# Power.net
KiCad netlist of a schematic drawn in Altium Designer
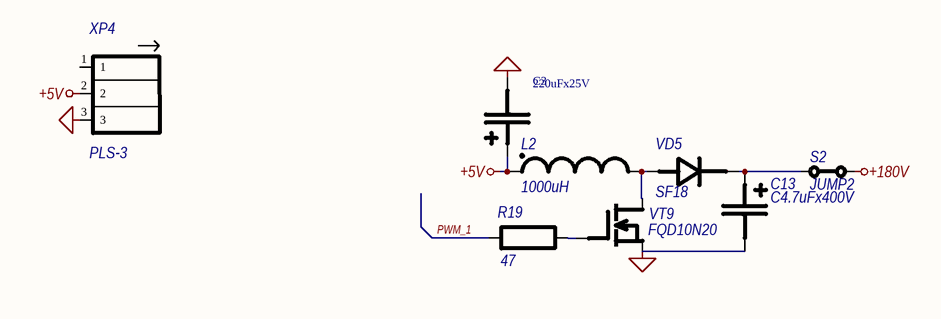
[diagram p0: Power.SchDoc]

(export (version "E")
  (design (tool "Eeschema 10.0.6"))
  (components
    (comp (ref "C3")
      (value "220uFx25V")
      (footprint "C8x11.5")
      (description "SY025M0220A3F-0811")
      (libsource (lib "sobol_lib") (part "C220uFx25V YAGEO SY"))
    )
    (comp (ref "C13")
      (value "C4.7uFx400V")
      (footprint "C10x16")
      (libsource (lib "sobol_lib") (part "C4.7uFx400V"))
    )
    (comp (ref "L2") (value "1000uH") (footprint "CHOKE1") (libsource (lib "sobol_lib") (part "CHOKE_1")))
    (comp (ref "R19")
      (value "47")
      (footprint "CR2012-0805")
      (libsource (lib "sobol_lib") (part "R0805-47R-5%"))
    )
    (comp (ref "S2") (value "JUMP2") (footprint "JUMP") (libsource (lib "sobol_lib") (part "JUMP2")))
    (comp (ref "VD5") (value "SF18") (footprint "DO-41") (libsource (lib "sobol_lib") (part "SF18")))
    (comp (ref "VT9") (value "FQD10N20") (footprint "TO-252") (libsource (lib "sobol_lib") (part "FQD10N20")))
    (comp (ref "XP4") (value "PLS-3") (footprint "PLS-3") (libsource (lib "sobol_lib") (part "PLS-3")))
  )
  (nets
    (net (code "1") (name "+5V") (class "Default")
      (node (ref "C3") (pin "1") (pinfunction "1_1") (pintype "passive"))
      (node (ref "L2") (pin "1") (pinfunction "1_1") (pintype "passive"))
      (node (ref "XP4") (pin "2") (pinfunction "2_2") (pintype "passive"))
    )
    (net (code "2") (name "+180V") (class "Default")
      (node (ref "S2") (pin "1") (pinfunction "1_1") (pintype "passive"))
    )
    (net (code "3") (name "/PWM_1") (class "Default")
      (node (ref "R19") (pin "1") (pinfunction "1_1") (pintype "passive"))
    )
    (net (code "4") (name "Net-(VD5-A)") (class "Default")
      (node (ref "L2") (pin "2") (pinfunction "2_2") (pintype "passive"))
      (node (ref "VD5") (pin "1") (pinfunction "A_1") (pintype "passive"))
      (node (ref "VT9") (pin "3") (pinfunction "D_3") (pintype "passive"))
    )
    (net (code "5") (name "Net-(VD5-K)") (class "Default")
      (node (ref "C13") (pin "1") (pinfunction "1_1") (pintype "passive"))
      (node (ref "S2") (pin "2") (pinfunction "2_2") (pintype "passive"))
      (node (ref "VD5") (pin "2") (pinfunction "K_2") (pintype "passive"))
    )
    (net (code "6") (name "Net-(VT9-G)") (class "Default")
      (node (ref "R19") (pin "2") (pinfunction "2_2") (pintype "passive"))
      (node (ref "VT9") (pin "1") (pinfunction "G_1") (pintype "passive"))
    )
    (net (code "7") (name "SGND") (class "Default")
      (node (ref "C13") (pin "2") (pinfunction "2_2") (pintype "passive"))
      (node (ref "C3") (pin "2") (pinfunction "2_2") (pintype "passive"))
      (node (ref "VT9") (pin "2") (pinfunction "S_2") (pintype "passive"))
      (node (ref "XP4") (pin "3") (pinfunction "3_3") (pintype "passive"))
    )
    (net (code "8") (name "unconnected-(XP4-Pad1)") (class "Default")
      (node (ref "XP4") (pin "1") (pinfunction "1_1") (pintype "passive"))
    )
  )
)
